# Interface.net
KiCad netlist of a schematic drawn in Altium Designer
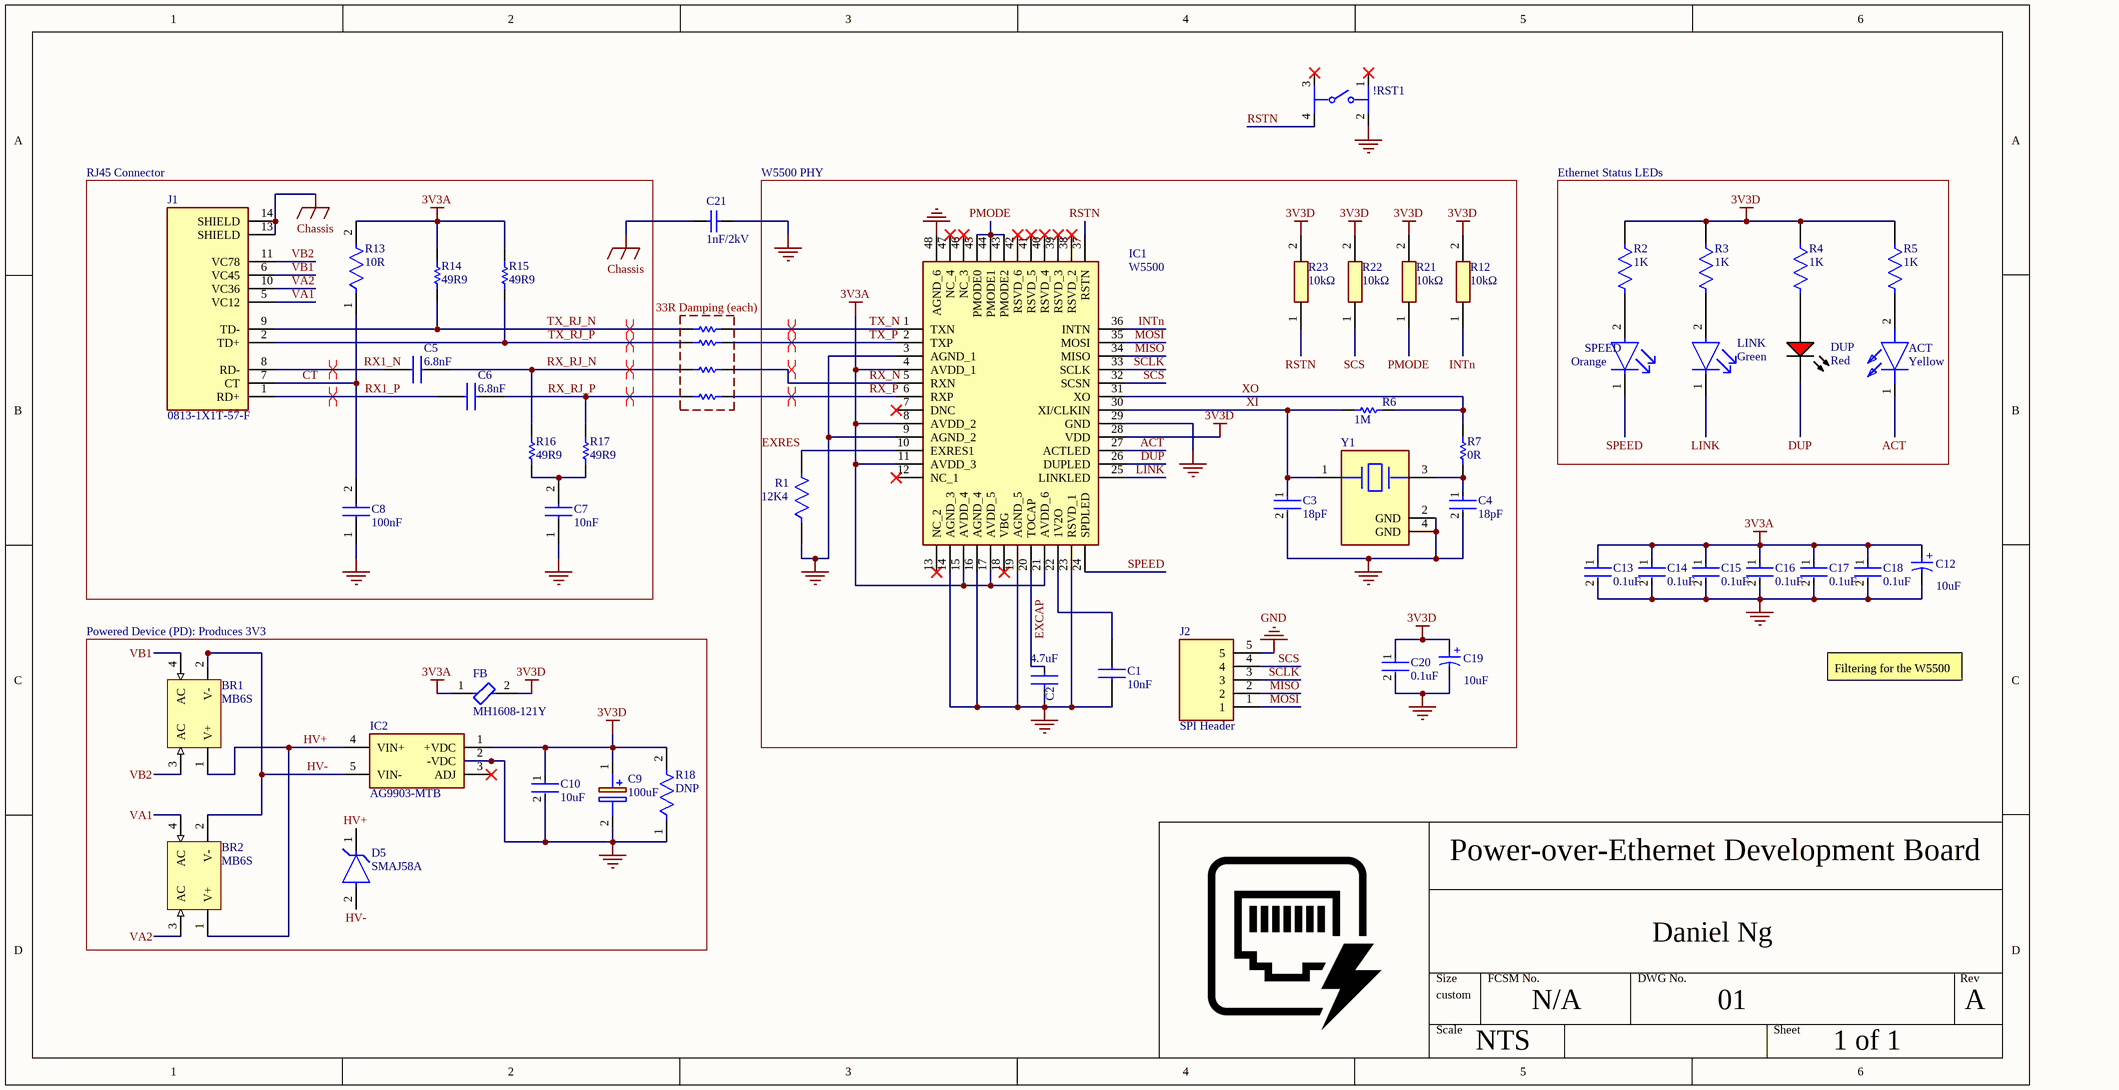
[diagram p0: Interface.SchDoc]

(export (version "E")
  (design (tool "Eeschema 10.0.6"))
  (components
    (comp (ref "!RST1")
      (value "PTS645SM43SMTR92LFS")
      (footprint "FP-PTS645SM43SMTR92LFS-MFG")
      (description "SWITCH TACTILE SPST-NO 0.05A 12V")
      (libsource (lib "Altium Content Vault") (part "1adf0dd01260c80cf25a44bfd6b99ba"))
    )
    (comp (ref "ACT")
      (value "Yellow")
      (footprint "LTSTC171KSKT")
      (description "LED")
      (fields
        (field (name "MANUFACTURER_PART_NUMBER") "LTST-C171KSKT")
        (field (name "MOUSER PART NUMBER") "859-LTST-C171KSKT")
      )
      (libsource (lib "*") (part "LTST-C171KSKT"))
    )
    (comp (ref "BR1")
      (value "MB6S")
      (footprint "FAIR-MBXS_V")
      (description "Bridge Rectifier, 0.5 A, -55 to 150 degC, 4-Pin SMD, RoHS, Tape and Reel")
      (fields (field (name "MANUFACTURER") "FairchildSemiconductor"))
      (libsource (lib "Altium Content Vault") (part "FAIR-MBXS-4"))
    )
    (comp (ref "BR2")
      (value "MB6S")
      (footprint "FAIR-MBXS_V")
      (description "Bridge Rectifier, 0.5 A, -55 to 150 degC, 4-Pin SMD, RoHS, Tape and Reel")
      (fields (field (name "MANUFACTURER") "FairchildSemiconductor"))
      (libsource (lib "Altium Content Vault") (part "FAIR-MBXS-4"))
    )
    (comp (ref "C1")
      (value "10nF")
      (footprint "C0603")
      (description "Capacitor")
      (fields
        (field (name "MANUFACTURER_PART_NUMBER") "C0603C103K4RECTU")
        (field (name "MOUSER PART NUMBER") "80-C0603C103K4RECTU")
      )
      (libsource (lib "*") (part "C0603C103K4RECTU"))
    )
    (comp (ref "C2")
      (value "4.7uF")
      (footprint "FP-CL10-IPC_C")
      (description "Cap Ceramic 4.7uF 10V X5R ±10% Pad SMD 0603 +85°C T/R")
      (fields (field (name "TOLERANCE") "10%"))
      (libsource (lib "") (part "b4654b650e69147ec39a6b967a45e02_1"))
    )
    (comp (ref "C3")
      (value "18pF")
      (footprint "FP-C0603C-CF-MFG")
      (description "CAP CER 18PF 50V C0G/NP0 0603")
      (fields (field (name "TOLERANCE") "0.05") (field (name "MANUFACTURER PART NUMBER") "C0603C180J5GACTU"))
      (libsource (lib "Altium Content Vault") (part "b4654b650e69147ec39a6b967a45e02"))
    )
    (comp (ref "C4")
      (value "18pF")
      (footprint "FP-C0603C-CF-MFG")
      (description "CAP CER 18PF 50V C0G/NP0 0603")
      (fields (field (name "TOLERANCE") "0.05") (field (name "MANUFACTURER PART NUMBER") "C0603C180J5GACTU"))
      (libsource (lib "Altium Content Vault") (part "b4654b650e69147ec39a6b967a45e02"))
    )
    (comp (ref "C5")
      (value "6.8nF")
      (footprint "SamacSys:CAPC1608X87N")
      (description "Capacitor")
      (fields (field (name "MANUFACTURER_PART_NUMBER") "C0603C682K4REC7411"))
      (libsource (lib "*") (part "C0603C682K4REC7411"))
    )
    (comp (ref "C6")
      (value "6.8nF")
      (footprint "SamacSys:CAPC1608X87N")
      (description "Capacitor")
      (fields (field (name "MANUFACTURER_PART_NUMBER") "C0603C682K4REC7411"))
      (libsource (lib "*") (part "C0603C682K4REC7411"))
    )
    (comp (ref "C7")
      (value "10nF")
      (footprint "C0805")
      (description "Capacitor")
      (fields (field (name "MANUFACTURER_PART_NUMBER") "C0805C103K5RECAUTO"))
      (libsource (lib "*") (part "C0805C103K5RECAUTO"))
    )
    (comp (ref "C8")
      (value "100nF")
      (footprint "SamacSys:CAPC1608X90N")
      (description "Capacitor")
      (fields
        (field (name "MANUFACTURER_PART_NUMBER") "CL10E104KC8VPNC")
        (field (name "MOUSER PART NUMBER") "187-CL10E104KC8VPNC")
      )
      (libsource (lib "*") (part "CL10E104KC8VPNC"))
    )
    (comp (ref "C9")
      (value "100uF")
      (footprint "EEHZT1E331UP")
      (description "Capacitor Polarised")
      (fields
        (field (name "MANUFACTURER_PART_NUMBER") "EEE-FP1V101AP")
        (field (name "MOUSER PART NUMBER") "667-EEE-FP1V101AP")
      )
      (libsource (lib "*") (part "EEE-FP1V101AP"))
    )
    (comp (ref "C10")
      (value "10uF")
      (footprint "FP-GRM188-0_2-IPC_A")
      (description "Chip Multilayer Ceramic Capacitors for General Purpose, 0603, 10uF, X5R, 15%, 10%, 25V")
      (libsource (lib "Altium Content Vault") (part "11868f565c42a9108669ba33697ecf6"))
    )
    (comp (ref "C12")
      (value "10uF")
      (footprint "WCAP-ASLU_D3H5.5")
      (description "Cap WCAP-ASLU Aluminum Electrolytic 10uF")
      (fields (field (name "TOLERANCE") "20%"))
      (libsource (lib "Altium Content Vault") (part "Capacitor_Polarized"))
    )
    (comp (ref "C13")
      (value "0.1uF")
      (footprint "FP-CC0603-DA-MFG")
      (description "CAP CER 0.1UF 50V X7R 0603")
      (fields (field (name "MANUFACTURER") "YAGEO") (field (name "VOLTAGE") "50 V"))
      (libsource (lib "Altium Content Vault") (part "11868f565c42a9108669ba33697ecf6"))
    )
    (comp (ref "C14")
      (value "0.1uF")
      (footprint "FP-CC0603-DA-MFG")
      (description "CAP CER 0.1UF 50V X7R 0603")
      (fields (field (name "MANUFACTURER") "YAGEO") (field (name "VOLTAGE") "50 V"))
      (libsource (lib "Altium Content Vault") (part "11868f565c42a9108669ba33697ecf6"))
    )
    (comp (ref "C15")
      (value "0.1uF")
      (footprint "FP-CC0603-DA-MFG")
      (description "CAP CER 0.1UF 50V X7R 0603")
      (fields (field (name "MANUFACTURER") "YAGEO") (field (name "VOLTAGE") "50 V"))
      (libsource (lib "Altium Content Vault") (part "11868f565c42a9108669ba33697ecf6"))
    )
    (comp (ref "C16")
      (value "0.1uF")
      (footprint "FP-CC0603-DA-MFG")
      (description "CAP CER 0.1UF 50V X7R 0603")
      (fields (field (name "MANUFACTURER") "YAGEO") (field (name "VOLTAGE") "50 V"))
      (libsource (lib "Altium Content Vault") (part "11868f565c42a9108669ba33697ecf6"))
    )
    (comp (ref "C17")
      (value "0.1uF")
      (footprint "FP-CC0603-DA-MFG")
      (description "CAP CER 0.1UF 50V X7R 0603")
      (fields (field (name "MANUFACTURER") "YAGEO") (field (name "VOLTAGE") "50 V"))
      (libsource (lib "Altium Content Vault") (part "11868f565c42a9108669ba33697ecf6"))
    )
    (comp (ref "C18")
      (value "0.1uF")
      (footprint "FP-CC0603-DA-MFG")
      (description "CAP CER 0.1UF 50V X7R 0603")
      (fields (field (name "MANUFACTURER") "YAGEO") (field (name "VOLTAGE") "50 V"))
      (libsource (lib "Altium Content Vault") (part "11868f565c42a9108669ba33697ecf6"))
    )
    (comp (ref "C19")
      (value "10uF")
      (footprint "WCAP-ASLU_D3H5.5")
      (description "Cap WCAP-ASLU Aluminum Electrolytic 10uF")
      (fields (field (name "TOLERANCE") "20%"))
      (libsource (lib "Altium Content Vault") (part "Capacitor_Polarized"))
    )
    (comp (ref "C20")
      (value "0.1uF")
      (footprint "FP-CC0603-DA-MFG")
      (description "CAP CER 0.1UF 50V X7R 0603")
      (fields (field (name "MANUFACTURER") "YAGEO") (field (name "VOLTAGE") "50 V"))
      (libsource (lib "Altium Content Vault") (part "11868f565c42a9108669ba33697ecf6"))
    )
    (comp (ref "C21")
      (value "1nF/2kV")
      (footprint "KEMT-1206-2_M")
      (description "CAP, Ceramic, 0.1 uF, +/- 10%, 50 V, -55 to 125 degC, 1206 (3216 Metric), RoHS, Tape and Reel")
      (fields (field (name "MANUFACTURER") "Kemet"))
      (libsource (lib "Altium Content Vault") (part "CAP-NP-2"))
    )
    (comp (ref "D5")
      (value "SMAJ58A")
      (footprint "FP-SMAJ-MFG")
      (description "TVS DIODE 58V 93.6V DO214AC")
      (fields (field (name "VOLTAGE") "58V"))
      (libsource (lib "Altium Content Vault") (part "f813f71cba58e380607f5dd3caf9714"))
    )
    (comp (ref "DUP")
      (value "Red")
      (footprint "LTST-C170KRKT_V")
      (description "LED Red, 75 mW, 54 mcd, -55 to 85 degC, 2-Pin SMD, RoHS, Tape and Reel")
      (fields (field (name "MANUFACTURER") "Lite-On"))
      (libsource (lib "Altium Content Vault") (part "LED-RED-AK-2"))
    )
    (comp (ref "FB")
      (value "MH1608-121Y")
      (footprint "FP-MH1608-MFG")
      (description "MH1608-121Y Ferrite Beads High Current Chip 120Ohm 25% 100MHz 2A 100mOhm DCR 0603 T/R")
      (fields (field (name "TOLERANCE") "25%"))
      (libsource (lib "Altium Content Vault") (part "5f30dd21d616792df468990f7003faa"))
    )
    (comp (ref "IC1")
      (value "W5500")
      (footprint "Timing_Gates_Custom:QFP50P900X900X160-48N")
      (description "Integrated Circuit")
      (libsource (lib "*") (part "W5500"))
    )
    (comp (ref "IC2")
      (value "AG9903-MTB")
      (footprint "SamacSys:AG9903MTB")
      (description "Integrated Circuit")
      (fields (field (name "MOUSER PART NUMBER") "480-AG9903-MTB"))
      (libsource (lib "SamacSys") (part "AG9903-MTB"))
    )
    (comp (ref "J1")
      (value "0813-1X1T-57-F")
      (footprint "Master_PCB:08131X1T57F")
      (description "Connector")
      (fields (field (name "MOUSER PART NUMBER") "530-0813-1X1T-57-F"))
      (libsource (lib "Master_SCH") (part "0813-1X1T-57-F"))
    )
    (comp (ref "J2")
      (value "SPI Header")
      (footprint "SamacSys:TSW-105-XX-YY-S")
      (description "Connector")
      (fields
        (field (name "MANUFACTURER_PART_NUMBER") "TSW-105-07-F-S")
        (field (name "MOUSER PART NUMBER") "200-TSW10507FS")
      )
      (libsource (lib "*") (part "TSW-105-07-F-S"))
    )
    (comp (ref "LINK")
      (value "Green")
      (footprint "FP-LTST-C170GKT-MFG")
      (description "LED GREEN CLEAR SMD")
      (fields (field (name "VOLTAGE") "5V"))
      (libsource (lib "Altium Content Vault") (part "8706943c75ba83719d021d2fdc84c58"))
    )
    (comp (ref "R1")
      (value "12K4")
      (footprint "FP-RC0603-0_55-MFG")
      (description "RES SMD 12.4K OHM 1% 1/10W 0603")
      (fields (field (name "TOLERANCE") "1%"))
      (libsource (lib "Altium Content Vault") (part "1029c3af85768c4190bb7ad29bc67b5"))
    )
    (comp (ref "R2")
      (value "1K")
      (footprint "FP-RC0603-0_55-IPC_C")
      (description "RES 1K OHM 1% 1/10W 0603")
      (fields (field (name "TOLERANCE") "1%"))
      (libsource (lib "Altium Content Vault") (part "1029c3af85768c4190bb7ad29bc67b5"))
    )
    (comp (ref "R3")
      (value "1K")
      (footprint "FP-RC0603-0_55-IPC_C")
      (description "RES 1K OHM 1% 1/10W 0603")
      (fields (field (name "TOLERANCE") "1%"))
      (libsource (lib "Altium Content Vault") (part "1029c3af85768c4190bb7ad29bc67b5"))
    )
    (comp (ref "R4")
      (value "1K")
      (footprint "FP-RC0603-0_55-IPC_C")
      (description "RES 1K OHM 1% 1/10W 0603")
      (fields (field (name "TOLERANCE") "1%"))
      (libsource (lib "Altium Content Vault") (part "1029c3af85768c4190bb7ad29bc67b5"))
    )
    (comp (ref "R5")
      (value "1K")
      (footprint "FP-RC0603-0_55-IPC_C")
      (description "RES 1K OHM 1% 1/10W 0603")
      (fields (field (name "TOLERANCE") "1%"))
      (libsource (lib "Altium Content Vault") (part "1029c3af85768c4190bb7ad29bc67b5"))
    )
    (comp (ref "R6")
      (value "1M")
      (footprint "RESC1608X55X25LL10T15")
      (description "Chip Resistor, 1 MOhm, +/- 1%, 100 mW, -55 to 155 degC, 0603 (1608 Metric), RoHS, Tape and Reel")
      (fields (field (name "TOLERANCE") "20%"))
      (libsource (lib "Altium Content Vault") (part "RES-2"))
    )
    (comp (ref "R7")
      (value "0R")
      (footprint "RESC1608X55X25ML10T15")
      (description "Chip Resistor, 0 Ohm, +/- 5%, 0.1 W, -55 to 155 degC, 0603 (1608 Metric), RoHS, Tape and Reel")
      (fields (field (name "TOLERANCE") "5%") (field (name "MANUFACTURER") "Yageo"))
      (libsource (lib "Altium Content Vault") (part "RES-2"))
    )
    (comp (ref "R8")
      (value "33R")
      (footprint "RESC2013X60X35LL10T20")
      (description "Chip Resistor, 33 Ohm, +/- 1%, 0.125 W, -55 to 155 degC, 0805 (2012 Metric), RoHS, Tape and Reel")
      (fields (field (name "MANUFACTURER") "Yageo"))
      (libsource (lib "Altium Content Vault") (part "RES-2"))
    )
    (comp (ref "R9")
      (value "33R")
      (footprint "RESC2013X60X35LL10T20")
      (description "Chip Resistor, 33 Ohm, +/- 1%, 0.125 W, -55 to 155 degC, 0805 (2012 Metric), RoHS, Tape and Reel")
      (fields (field (name "MANUFACTURER") "Yageo"))
      (libsource (lib "Altium Content Vault") (part "RES-2"))
    )
    (comp (ref "R10")
      (value "33R")
      (footprint "RESC2013X60X35LL10T20")
      (description "Chip Resistor, 33 Ohm, +/- 1%, 0.125 W, -55 to 155 degC, 0805 (2012 Metric), RoHS, Tape and Reel")
      (fields (field (name "MANUFACTURER") "Yageo"))
      (libsource (lib "Altium Content Vault") (part "RES-2"))
    )
    (comp (ref "R11")
      (value "33R")
      (footprint "RESC2013X60X35LL10T20")
      (description "Chip Resistor, 33 Ohm, +/- 1%, 0.125 W, -55 to 155 degC, 0805 (2012 Metric), RoHS, Tape and Reel")
      (fields (field (name "MANUFACTURER") "Yageo"))
      (libsource (lib "Altium Content Vault") (part "RES-2"))
    )
    (comp (ref "R12")
      (value "10kΩ")
      (footprint "RESC1608X55N")
      (description "Resistor")
      (fields (field (name "MANUFACTURER_PART_NUMBER") "RC0603FR0710KL"))
      (libsource (lib "*") (part "RC0603FR0710KL"))
    )
    (comp (ref "R13")
      (value "10R")
      (footprint "FP-RC0603-0_55-IPC_C")
      (description "RES 10K OHM 1% 1/10W 0603")
      (fields (field (name "TOLERANCE") "1%"))
      (libsource (lib "") (part "1029c3af85768c4190bb7ad29bc67b5_1"))
    )
    (comp (ref "R14")
      (value "49R9")
      (footprint "RESC1608X55X30ML15T15")
      (fields (field (name "MANUFACTURER") "Panasonic") (field (name "PART NUMBER") "ERJ-3EKF49R9V"))
      (libsource (lib "Altium Content Vault") (part "RES"))
    )
    (comp (ref "R15")
      (value "49R9")
      (footprint "RESC1608X55X30ML15T15")
      (fields (field (name "MANUFACTURER") "Panasonic") (field (name "PART NUMBER") "ERJ-3EKF49R9V"))
      (libsource (lib "Altium Content Vault") (part "RES"))
    )
    (comp (ref "R16")
      (value "49R9")
      (footprint "RESC1608X55X30ML15T15")
      (fields (field (name "MANUFACTURER") "Panasonic") (field (name "PART NUMBER") "ERJ-3EKF49R9V"))
      (libsource (lib "Altium Content Vault") (part "RES"))
    )
    (comp (ref "R17")
      (value "49R9")
      (footprint "RESC1608X55X30ML15T15")
      (fields (field (name "MANUFACTURER") "Panasonic") (field (name "PART NUMBER") "ERJ-3EKF49R9V"))
      (libsource (lib "Altium Content Vault") (part "RES"))
    )
    (comp (ref "R18")
      (value "DNP")
      (footprint "FP-AF0805-IPC_C")
      (description "Anti-Sulfurated Chip Resistor Automotive Grade 130Ω 1% 0.125W ±100ppm/°C 0805")
      (fields (field (name "TOLERANCE") "1%"))
      (libsource (lib "") (part "1029c3af85768c4190bb7ad29bc67b5_1"))
    )
    (comp (ref "R21")
      (value "10kΩ")
      (footprint "RESC1608X55N")
      (description "Resistor")
      (fields (field (name "MANUFACTURER_PART_NUMBER") "RC0603FR0710KL"))
      (libsource (lib "*") (part "RC0603FR0710KL"))
    )
    (comp (ref "R22")
      (value "10kΩ")
      (footprint "RESC1608X55N")
      (description "Resistor")
      (fields (field (name "MANUFACTURER_PART_NUMBER") "RC0603FR0710KL"))
      (libsource (lib "*") (part "RC0603FR0710KL"))
    )
    (comp (ref "R23")
      (value "10kΩ")
      (footprint "RESC1608X55N")
      (description "Resistor")
      (fields (field (name "MANUFACTURER_PART_NUMBER") "RC0603FR0710KL"))
      (libsource (lib "*") (part "RC0603FR0710KL"))
    )
    (comp (ref "SPEED")
      (value "Orange")
      (footprint "FP-LTST-C170KFKT-MFG")
      (description "LED ORANGE CLEAR SMD")
      (libsource (lib "Altium Content Vault") (part "8706943c75ba83719d021d2fdc84c58"))
    )
    (comp (ref "Y1")
      (value "ABM8-25.000MHZ-B2-T")
      (footprint "FP-ABM8-MFG")
      (description "Crystal 25MHz ±20ppm 18pF SMD-4 3.2mm x 2.5mm")
      (fields (field (name "TOLERANCE") "20ppm"))
      (libsource (lib "Altium Content Vault") (part "dfdb7f9a12507849fb681da9a70121c"))
    )
  )
  (nets
    (net (code "1") (name "/ACT") (class "Default")
      (node (ref "ACT") (pin "1") (pinfunction "K_1") (pintype "passive"))
      (node (ref "IC1") (pin "27") (pinfunction "ACTLED_27") (pintype "passive"))
    )
    (net (code "2") (name "/CT") (class "Default")
      (node (ref "C8") (pin "2") (pinfunction "2_2") (pintype "passive"))
      (node (ref "J1") (pin "7") (pinfunction "CT_7") (pintype "passive"))
      (node (ref "R13") (pin "1") (pinfunction "1_1") (pintype "passive"))
    )
    (net (code "3") (name "/DUP") (class "Default")
      (node (ref "DUP") (pin "2") (pinfunction "K_2") (pintype "passive"))
      (node (ref "IC1") (pin "26") (pinfunction "DUPLED_26") (pintype "passive"))
    )
    (net (code "4") (name "/EXCAP") (class "Default")
      (node (ref "C2") (pin "2") (pinfunction "2_2") (pintype "passive"))
      (node (ref "IC1") (pin "20") (pinfunction "TOCAP_20") (pintype "passive"))
    )
    (net (code "5") (name "/EXRES") (class "Default")
      (node (ref "IC1") (pin "10") (pinfunction "EXRES1_10") (pintype "passive"))
      (node (ref "R1") (pin "2") (pinfunction "2_2") (pintype "passive"))
    )
    (net (code "6") (name "/HV+") (class "Default")
      (node (ref "BR1") (pin "1") (pinfunction "V+_1") (pintype "power_in"))
      (node (ref "BR2") (pin "1") (pinfunction "V+_1") (pintype "power_in"))
      (node (ref "D5") (pin "1") (pinfunction "C_1") (pintype "passive"))
      (node (ref "IC2") (pin "4") (pinfunction "VIN+_4") (pintype "passive"))
    )
    (net (code "7") (name "/HV-") (class "Default")
      (node (ref "BR1") (pin "2") (pinfunction "V-_2") (pintype "power_in"))
      (node (ref "BR2") (pin "2") (pinfunction "V-_2") (pintype "power_in"))
      (node (ref "D5") (pin "2") (pinfunction "A_2") (pintype "passive"))
      (node (ref "IC2") (pin "5") (pinfunction "VIN-_5") (pintype "passive"))
    )
    (net (code "8") (name "/INTn") (class "Default")
      (node (ref "IC1") (pin "36") (pinfunction "INTN_36") (pintype "passive"))
      (node (ref "R12") (pin "1") (pinfunction "1_1") (pintype "passive"))
    )
    (net (code "9") (name "/LINK") (class "Default")
      (node (ref "IC1") (pin "25") (pinfunction "LINKLED_25") (pintype "passive"))
      (node (ref "LINK") (pin "1") (pinfunction "C_1") (pintype "passive"))
    )
    (net (code "10") (name "/MISO") (class "Default")
      (node (ref "IC1") (pin "34") (pinfunction "MISO_34") (pintype "passive"))
      (node (ref "J2") (pin "2") (pinfunction "2_2") (pintype "passive"))
    )
    (net (code "11") (name "/MOSI") (class "Default")
      (node (ref "IC1") (pin "35") (pinfunction "MOSI_35") (pintype "passive"))
      (node (ref "J2") (pin "1") (pinfunction "1_1") (pintype "passive"))
    )
    (net (code "12") (name "/PMODE") (class "Default")
      (node (ref "IC1") (pin "43") (pinfunction "PMODE2_43") (pintype "passive"))
      (node (ref "IC1") (pin "44") (pinfunction "PMODE1_44") (pintype "passive"))
      (node (ref "IC1") (pin "45") (pinfunction "PMODE0_45") (pintype "passive"))
      (node (ref "R21") (pin "1") (pinfunction "1_1") (pintype "passive"))
    )
    (net (code "13") (name "/RSTN") (class "Default")
      (node (ref "!RST1") (pin "4") (pinfunction "4_4") (pintype "passive"))
      (node (ref "IC1") (pin "37") (pinfunction "RSTN_37") (pintype "passive"))
      (node (ref "R23") (pin "1") (pinfunction "1_1") (pintype "passive"))
    )
    (net (code "14") (name "/RX1_N") (class "Default")
      (node (ref "C5") (pin "1") (pinfunction "1_1") (pintype "passive"))
      (node (ref "J1") (pin "8") (pinfunction "RD-_8") (pintype "passive"))
    )
    (net (code "15") (name "/RX1_P") (class "Default")
      (node (ref "C6") (pin "1") (pinfunction "1_1") (pintype "passive"))
      (node (ref "J1") (pin "1") (pinfunction "RD+_1") (pintype "passive"))
    )
    (net (code "16") (name "/RX_N") (class "Default")
      (node (ref "IC1") (pin "5") (pinfunction "RXN_5") (pintype "passive"))
      (node (ref "R10") (pin "2") (pinfunction "2_2") (pintype "passive"))
    )
    (net (code "17") (name "/RX_P") (class "Default")
      (node (ref "IC1") (pin "6") (pinfunction "RXP_6") (pintype "passive"))
      (node (ref "R11") (pin "2") (pinfunction "2_2") (pintype "passive"))
    )
    (net (code "18") (name "/RX_RJ_N") (class "Default")
      (node (ref "C5") (pin "2") (pinfunction "2_2") (pintype "passive"))
      (node (ref "R10") (pin "1") (pinfunction "1_1") (pintype "passive"))
      (node (ref "R16") (pin "2") (pinfunction "2_2") (pintype "passive"))
    )
    (net (code "19") (name "/RX_RJ_P") (class "Default")
      (node (ref "C6") (pin "2") (pinfunction "2_2") (pintype "passive"))
      (node (ref "R11") (pin "1") (pinfunction "1_1") (pintype "passive"))
      (node (ref "R17") (pin "2") (pinfunction "2_2") (pintype "passive"))
    )
    (net (code "20") (name "/SCLK") (class "Default")
      (node (ref "IC1") (pin "33") (pinfunction "SCLK_33") (pintype "passive"))
      (node (ref "J2") (pin "3") (pinfunction "3_3") (pintype "passive"))
    )
    (net (code "21") (name "/SCS") (class "Default")
      (node (ref "IC1") (pin "32") (pinfunction "SCSN_32") (pintype "passive"))
      (node (ref "J2") (pin "4") (pinfunction "4_4") (pintype "passive"))
      (node (ref "R22") (pin "1") (pinfunction "1_1") (pintype "passive"))
    )
    (net (code "22") (name "/SPEED") (class "Default")
      (node (ref "IC1") (pin "24") (pinfunction "SPDLED_24") (pintype "passive"))
      (node (ref "SPEED") (pin "1") (pinfunction "C_1") (pintype "passive"))
    )
    (net (code "23") (name "/TX_N") (class "Default")
      (node (ref "IC1") (pin "1") (pinfunction "TXN_1") (pintype "passive"))
      (node (ref "R8") (pin "2") (pinfunction "2_2") (pintype "passive"))
    )
    (net (code "24") (name "/TX_P") (class "Default")
      (node (ref "IC1") (pin "2") (pinfunction "TXP_2") (pintype "passive"))
      (node (ref "R9") (pin "2") (pinfunction "2_2") (pintype "passive"))
    )
    (net (code "25") (name "/TX_RJ_N") (class "Default")
      (node (ref "J1") (pin "9") (pinfunction "TD-_9") (pintype "passive"))
      (node (ref "R14") (pin "1") (pinfunction "1_1") (pintype "passive"))
      (node (ref "R8") (pin "1") (pinfunction "1_1") (pintype "passive"))
    )
    (net (code "26") (name "/TX_RJ_P") (class "Default")
      (node (ref "J1") (pin "2") (pinfunction "TD+_2") (pintype "passive"))
      (node (ref "R15") (pin "1") (pinfunction "1_1") (pintype "passive"))
      (node (ref "R9") (pin "1") (pinfunction "1_1") (pintype "passive"))
    )
    (net (code "27") (name "/VA1") (class "Default")
      (node (ref "BR2") (pin "4") (pinfunction "AC_4") (pintype "input"))
      (node (ref "J1") (pin "5") (pinfunction "VC12_5") (pintype "passive"))
    )
    (net (code "28") (name "/VA2") (class "Default")
      (node (ref "BR2") (pin "3") (pinfunction "AC_3") (pintype "input"))
      (node (ref "J1") (pin "10") (pinfunction "VC36_10") (pintype "passive"))
    )
    (net (code "29") (name "/VB1") (class "Default")
      (node (ref "BR1") (pin "4") (pinfunction "AC_4") (pintype "input"))
      (node (ref "J1") (pin "6") (pinfunction "VC45_6") (pintype "passive"))
    )
    (net (code "30") (name "/VB2") (class "Default")
      (node (ref "BR1") (pin "3") (pinfunction "AC_3") (pintype "input"))
      (node (ref "J1") (pin "11") (pinfunction "VC78_11") (pintype "passive"))
    )
    (net (code "31") (name "/XI") (class "Default")
      (node (ref "C3") (pin "1") (pinfunction "1_1") (pintype "passive"))
      (node (ref "IC1") (pin "30") (pinfunction "XI/CLKIN_30") (pintype "passive"))
      (node (ref "R6") (pin "1") (pinfunction "1_1") (pintype "passive"))
      (node (ref "Y1") (pin "1") (pinfunction "1_1") (pintype "passive"))
    )
    (net (code "32") (name "/XO") (class "Default")
      (node (ref "IC1") (pin "31") (pinfunction "XO_31") (pintype "passive"))
      (node (ref "R6") (pin "2") (pinfunction "2_2") (pintype "passive"))
      (node (ref "R7") (pin "2") (pinfunction "2_2") (pintype "passive"))
    )
    (net (code "33") (name "3V3A") (class "Default")
      (node (ref "C12") (pin "1") (pinfunction "P_1") (pintype "passive"))
      (node (ref "C13") (pin "1") (pinfunction "1_1") (pintype "passive"))
      (node (ref "C14") (pin "1") (pinfunction "1_1") (pintype "passive"))
      (node (ref "C15") (pin "1") (pinfunction "1_1") (pintype "passive"))
      (node (ref "C16") (pin "1") (pinfunction "1_1") (pintype "passive"))
      (node (ref "C17") (pin "1") (pinfunction "1_1") (pintype "passive"))
      (node (ref "C18") (pin "1") (pinfunction "1_1") (pintype "passive"))
      (node (ref "FB") (pin "1") (pinfunction "1_1") (pintype "passive"))
      (node (ref "IC1") (pin "11") (pinfunction "AVDD_3_11") (pintype "passive"))
      (node (ref "IC1") (pin "15") (pinfunction "AVDD_4_15") (pintype "passive"))
      (node (ref "IC1") (pin "17") (pinfunction "AVDD_5_17") (pintype "passive"))
      (node (ref "IC1") (pin "21") (pinfunction "AVDD_6_21") (pintype "passive"))
      (node (ref "IC1") (pin "4") (pinfunction "AVDD_1_4") (pintype "passive"))
      (node (ref "IC1") (pin "8") (pinfunction "AVDD_2_8") (pintype "passive"))
      (node (ref "R13") (pin "2") (pinfunction "2_2") (pintype "passive"))
      (node (ref "R14") (pin "2") (pinfunction "2_2") (pintype "passive"))
      (node (ref "R15") (pin "2") (pinfunction "2_2") (pintype "passive"))
    )
    (net (code "34") (name "3V3D") (class "Default")
      (node (ref "C10") (pin "1") (pinfunction "1_1") (pintype "passive"))
      (node (ref "C19") (pin "1") (pinfunction "P_1") (pintype "passive"))
      (node (ref "C20") (pin "1") (pinfunction "1_1") (pintype "passive"))
      (node (ref "C9") (pin "1") (pinfunction "+_1") (pintype "passive"))
      (node (ref "FB") (pin "2") (pinfunction "2_2") (pintype "passive"))
      (node (ref "IC1") (pin "28") (pinfunction "VDD_28") (pintype "passive"))
      (node (ref "IC2") (pin "1") (pinfunction "+VDC_1") (pintype "passive"))
      (node (ref "R12") (pin "2") (pinfunction "2_2") (pintype "passive"))
      (node (ref "R18") (pin "2") (pinfunction "2_2") (pintype "passive"))
      (node (ref "R2") (pin "1") (pinfunction "1_1") (pintype "passive"))
      (node (ref "R21") (pin "2") (pinfunction "2_2") (pintype "passive"))
      (node (ref "R22") (pin "2") (pinfunction "2_2") (pintype "passive"))
      (node (ref "R23") (pin "2") (pinfunction "2_2") (pintype "passive"))
      (node (ref "R3") (pin "1") (pinfunction "1_1") (pintype "passive"))
      (node (ref "R4") (pin "1") (pinfunction "1_1") (pintype "passive"))
      (node (ref "R5") (pin "1") (pinfunction "1_1") (pintype "passive"))
    )
    (net (code "35") (name "Chassis") (class "Default")
      (node (ref "C21") (pin "1") (pinfunction "1_1") (pintype "passive"))
      (node (ref "J1") (pin "13") (pinfunction "SHIELD_13") (pintype "passive"))
      (node (ref "J1") (pin "14") (pinfunction "SHIELD_14") (pintype "passive"))
    )
    (net (code "36") (name "GND") (class "Default")
      (node (ref "!RST1") (pin "2") (pinfunction "2_2") (pintype "passive"))
      (node (ref "C1") (pin "1") (pinfunction "1_1") (pintype "passive"))
      (node (ref "C10") (pin "2") (pinfunction "2_2") (pintype "passive"))
      (node (ref "C12") (pin "2") (pinfunction "N_2") (pintype "passive"))
      (node (ref "C13") (pin "2") (pinfunction "2_2") (pintype "passive"))
      (node (ref "C14") (pin "2") (pinfunction "2_2") (pintype "passive"))
      (node (ref "C15") (pin "2") (pinfunction "2_2") (pintype "passive"))
      (node (ref "C16") (pin "2") (pinfunction "2_2") (pintype "passive"))
      (node (ref "C17") (pin "2") (pinfunction "2_2") (pintype "passive"))
      (node (ref "C18") (pin "2") (pinfunction "2_2") (pintype "passive"))
      (node (ref "C19") (pin "2") (pinfunction "N_2") (pintype "passive"))
      (node (ref "C2") (pin "1") (pinfunction "1_1") (pintype "passive"))
      (node (ref "C20") (pin "2") (pinfunction "2_2") (pintype "passive"))
      (node (ref "C21") (pin "2") (pinfunction "2_2") (pintype "passive"))
      (node (ref "C3") (pin "2") (pinfunction "2_2") (pintype "passive"))
      (node (ref "C4") (pin "2") (pinfunction "2_2") (pintype "passive"))
      (node (ref "C7") (pin "1") (pinfunction "1_1") (pintype "passive"))
      (node (ref "C8") (pin "1") (pinfunction "1_1") (pintype "passive"))
      (node (ref "C9") (pin "2") (pinfunction "-_2") (pintype "passive"))
      (node (ref "IC1") (pin "14") (pinfunction "AGND_3_14") (pintype "passive"))
      (node (ref "IC1") (pin "16") (pinfunction "AGND_4_16") (pintype "passive"))
      (node (ref "IC1") (pin "19") (pinfunction "AGND_5_19") (pintype "passive"))
      (node (ref "IC1") (pin "23") (pinfunction "RSVD_1_23") (pintype "passive"))
      (node (ref "IC1") (pin "29") (pinfunction "GND_29") (pintype "passive"))
      (node (ref "IC1") (pin "3") (pinfunction "AGND_1_3") (pintype "passive"))
      (node (ref "IC1") (pin "48") (pinfunction "AGND_6_48") (pintype "passive"))
      (node (ref "IC1") (pin "9") (pinfunction "AGND_2_9") (pintype "passive"))
      (node (ref "IC2") (pin "2") (pinfunction "-VDC_2") (pintype "passive"))
      (node (ref "J2") (pin "5") (pinfunction "5_5") (pintype "passive"))
      (node (ref "R1") (pin "1") (pinfunction "1_1") (pintype "passive"))
      (node (ref "R18") (pin "1") (pinfunction "1_1") (pintype "passive"))
      (node (ref "Y1") (pin "2") (pinfunction "GND_2") (pintype "power_in"))
      (node (ref "Y1") (pin "4") (pinfunction "GND_4") (pintype "power_in"))
    )
    (net (code "37") (name "Net-(ACT-A)") (class "Default")
      (node (ref "ACT") (pin "2") (pinfunction "A_2") (pintype "passive"))
      (node (ref "R5") (pin "2") (pinfunction "2_2") (pintype "passive"))
    )
    (net (code "38") (name "Net-(C4-Pad1)") (class "Default")
      (node (ref "C4") (pin "1") (pinfunction "1_1") (pintype "passive"))
      (node (ref "R7") (pin "1") (pinfunction "1_1") (pintype "passive"))
      (node (ref "Y1") (pin "3") (pinfunction "3_3") (pintype "passive"))
    )
    (net (code "39") (name "Net-(C7-Pad2)") (class "Default")
      (node (ref "C7") (pin "2") (pinfunction "2_2") (pintype "passive"))
      (node (ref "R16") (pin "1") (pinfunction "1_1") (pintype "passive"))
      (node (ref "R17") (pin "1") (pinfunction "1_1") (pintype "passive"))
    )
    (net (code "40") (name "Net-(DUP-A)") (class "Default")
      (node (ref "DUP") (pin "1") (pinfunction "A_1") (pintype "passive"))
      (node (ref "R4") (pin "2") (pinfunction "2_2") (pintype "passive"))
    )
    (net (code "41") (name "Net-(IC1-1V2O)") (class "Default")
      (node (ref "C1") (pin "2") (pinfunction "2_2") (pintype "passive"))
      (node (ref "IC1") (pin "22") (pinfunction "1V2O_22") (pintype "passive"))
    )
    (net (code "42") (name "Net-(LINK-A)") (class "Default")
      (node (ref "LINK") (pin "2") (pinfunction "A_2") (pintype "passive"))
      (node (ref "R3") (pin "2") (pinfunction "2_2") (pintype "passive"))
    )
    (net (code "43") (name "Net-(SPEED-A)") (class "Default")
      (node (ref "R2") (pin "2") (pinfunction "2_2") (pintype "passive"))
      (node (ref "SPEED") (pin "2") (pinfunction "A_2") (pintype "passive"))
    )
    (net (code "44") (name "unconnected-(!RST1-Pad1)") (class "Default")
      (node (ref "!RST1") (pin "1") (pinfunction "1_1") (pintype "passive+no_connect"))
    )
    (net (code "45") (name "unconnected-(!RST1-Pad3)") (class "Default")
      (node (ref "!RST1") (pin "3") (pinfunction "3_3") (pintype "passive+no_connect"))
    )
    (net (code "46") (name "unconnected-(IC1-DNC-Pad7)") (class "Default")
      (node (ref "IC1") (pin "7") (pinfunction "DNC_7") (pintype "passive+no_connect"))
    )
    (net (code "47") (name "unconnected-(IC1-NC_1-Pad12)") (class "Default")
      (node (ref "IC1") (pin "12") (pinfunction "NC_1_12") (pintype "passive+no_connect"))
    )
    (net (code "48") (name "unconnected-(IC1-NC_2-Pad13)") (class "Default")
      (node (ref "IC1") (pin "13") (pinfunction "NC_2_13") (pintype "passive+no_connect"))
    )
    (net (code "49") (name "unconnected-(IC1-NC_3-Pad46)") (class "Default")
      (node (ref "IC1") (pin "46") (pinfunction "NC_3_46") (pintype "passive+no_connect"))
    )
    (net (code "50") (name "unconnected-(IC1-NC_4-Pad47)") (class "Default")
      (node (ref "IC1") (pin "47") (pinfunction "NC_4_47") (pintype "passive+no_connect"))
    )
    (net (code "51") (name "unconnected-(IC1-RSVD_2-Pad38)") (class "Default")
      (node (ref "IC1") (pin "38") (pinfunction "RSVD_2_38") (pintype "passive+no_connect"))
    )
    (net (code "52") (name "unconnected-(IC1-RSVD_3-Pad39)") (class "Default")
      (node (ref "IC1") (pin "39") (pinfunction "RSVD_3_39") (pintype "passive+no_connect"))
    )
    (net (code "53") (name "unconnected-(IC1-RSVD_4-Pad40)") (class "Default")
      (node (ref "IC1") (pin "40") (pinfunction "RSVD_4_40") (pintype "passive+no_connect"))
    )
    (net (code "54") (name "unconnected-(IC1-RSVD_5-Pad41)") (class "Default")
      (node (ref "IC1") (pin "41") (pinfunction "RSVD_5_41") (pintype "passive+no_connect"))
    )
    (net (code "55") (name "unconnected-(IC1-RSVD_6-Pad42)") (class "Default")
      (node (ref "IC1") (pin "42") (pinfunction "RSVD_6_42") (pintype "passive+no_connect"))
    )
    (net (code "56") (name "unconnected-(IC1-VBG-Pad18)") (class "Default")
      (node (ref "IC1") (pin "18") (pinfunction "VBG_18") (pintype "passive+no_connect"))
    )
    (net (code "57") (name "unconnected-(IC2-ADJ-Pad3)") (class "Default")
      (node (ref "IC2") (pin "3") (pinfunction "ADJ_3") (pintype "passive+no_connect"))
    )
  )
)
